# tutorial5.net
KiCad netlist of a schematic drawn in EAGLE
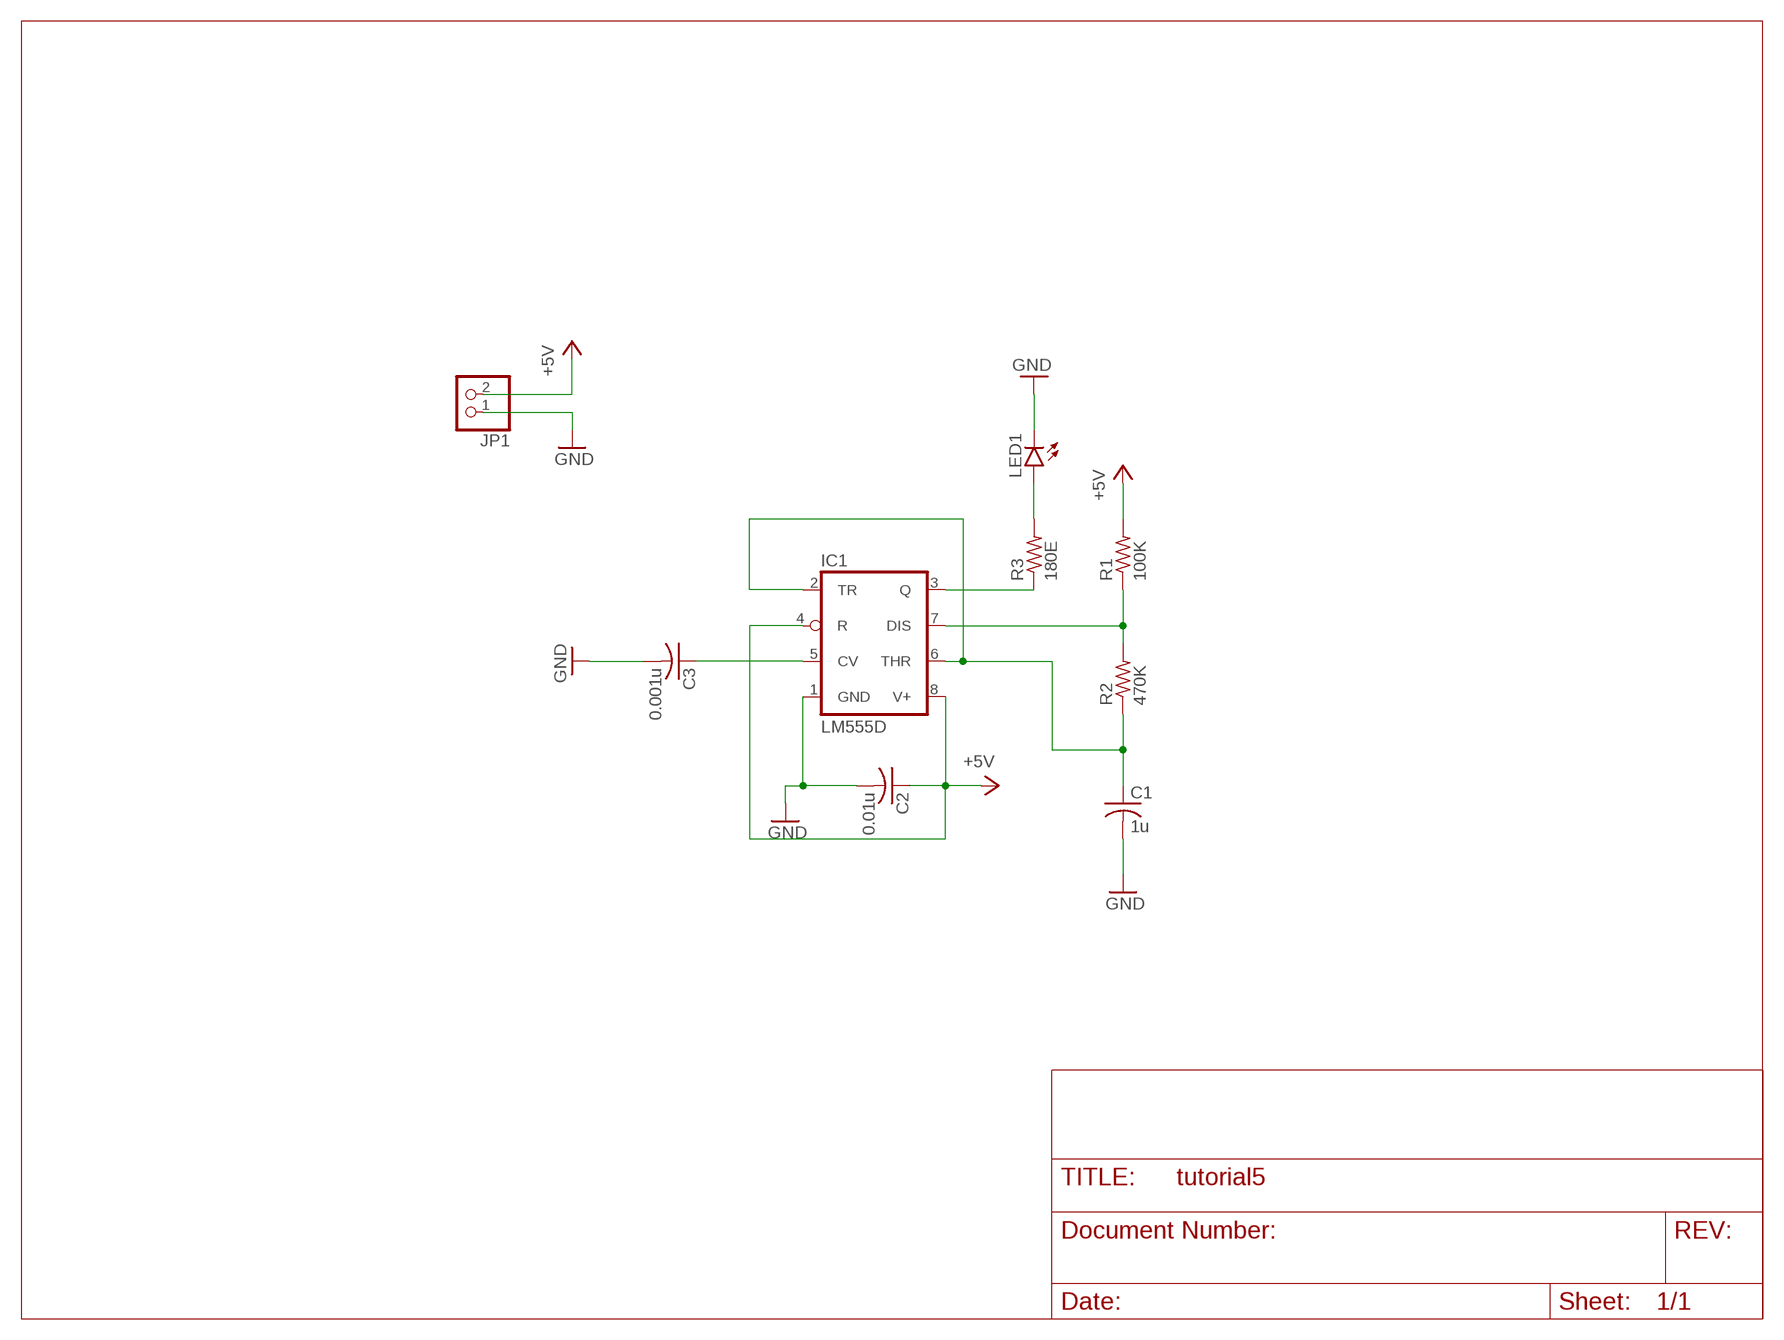
[diagram p0: schematic, sheet 1]

(export (version "E")
  (design (tool "Eeschema 10.0.6"))
  (components
    (comp (ref "C1")
      (value "1u")
      (footprint "eagle-import:C0805")
      (libsource (lib "eagle-import") (part "C-USC0805"))
    )
    (comp (ref "C2")
      (value "0.01u")
      (footprint "eagle-import:C0805")
      (libsource (lib "eagle-import") (part "C-USC0805"))
    )
    (comp (ref "C3")
      (value "0.001u")
      (footprint "eagle-import:C0805")
      (libsource (lib "eagle-import") (part "C-USC0805"))
    )
    (comp (ref "IC1")
      (value "LM555D")
      (footprint "eagle-import:SO08")
      (libsource (lib "eagle-import") (part "555DLM"))
    )
    (comp (ref "JP1")
      (value "PINHD-1X2")
      (footprint "eagle-import:1X02")
      (libsource (lib "eagle-import") (part "PINHD-1X2"))
    )
    (comp (ref "LED1")
      (value "LED5MM")
      (footprint "eagle-import:LED5MM")
      (libsource (lib "eagle-import") (part "LED5MM"))
    )
    (comp (ref "R1")
      (value "100K")
      (footprint "eagle-import:R0805")
      (libsource (lib "eagle-import") (part "R-US_R0805"))
    )
    (comp (ref "R2")
      (value "470K")
      (footprint "eagle-import:R0805")
      (libsource (lib "eagle-import") (part "R-US_R0805"))
    )
    (comp (ref "R3")
      (value "180E")
      (footprint "eagle-import:R0805")
      (libsource (lib "eagle-import") (part "R-US_R0805"))
    )
  )
  (nets
    (net (code "1") (name "+5V") (class "Default")
      (node (ref "C2") (pin "1") (pinfunction "1_1") (pintype "passive"))
      (node (ref "IC1") (pin "4") (pinfunction "R_4") (pintype "input"))
      (node (ref "IC1") (pin "8") (pinfunction "V+_8") (pintype "power_in"))
      (node (ref "JP1") (pin "2") (pinfunction "2_2") (pintype "passive"))
      (node (ref "R1") (pin "2") (pinfunction "2_2") (pintype "passive"))
    )
    (net (code "2") (name "GND") (class "Default")
      (node (ref "C1") (pin "2") (pinfunction "2_2") (pintype "passive"))
      (node (ref "C2") (pin "2") (pinfunction "2_2") (pintype "passive"))
      (node (ref "C3") (pin "2") (pinfunction "2_2") (pintype "passive"))
      (node (ref "IC1") (pin "1") (pinfunction "GND_1") (pintype "power_in"))
      (node (ref "JP1") (pin "1") (pinfunction "1_1") (pintype "passive"))
      (node (ref "LED1") (pin "K") (pinfunction "C_K") (pintype "passive"))
    )
    (net (code "3") (name "Net-(IC1-CV)") (class "Default")
      (node (ref "C3") (pin "1") (pinfunction "1_1") (pintype "passive"))
      (node (ref "IC1") (pin "5") (pinfunction "CV_5") (pintype "input"))
    )
    (net (code "4") (name "Net-(IC1-DIS)") (class "Default")
      (node (ref "IC1") (pin "7") (pinfunction "DIS_7") (pintype "input"))
      (node (ref "R1") (pin "1") (pinfunction "1_1") (pintype "passive"))
      (node (ref "R2") (pin "2") (pinfunction "2_2") (pintype "passive"))
    )
    (net (code "5") (name "Net-(IC1-Q)") (class "Default")
      (node (ref "IC1") (pin "3") (pinfunction "Q_3") (pintype "output"))
      (node (ref "R3") (pin "1") (pinfunction "1_1") (pintype "passive"))
    )
    (net (code "6") (name "Net-(IC1-THR)") (class "Default")
      (node (ref "C1") (pin "1") (pinfunction "1_1") (pintype "passive"))
      (node (ref "IC1") (pin "2") (pinfunction "TR_2") (pintype "input"))
      (node (ref "IC1") (pin "6") (pinfunction "THR_6") (pintype "input"))
      (node (ref "R2") (pin "1") (pinfunction "1_1") (pintype "passive"))
    )
    (net (code "7") (name "Net-(LED1-PadA)") (class "Default")
      (node (ref "LED1") (pin "A") (pinfunction "A_A") (pintype "passive"))
      (node (ref "R3") (pin "2") (pinfunction "2_2") (pintype "passive"))
    )
  )
)
